# IMU_Sensor.net
KiCad netlist of a schematic drawn in Altium Designer
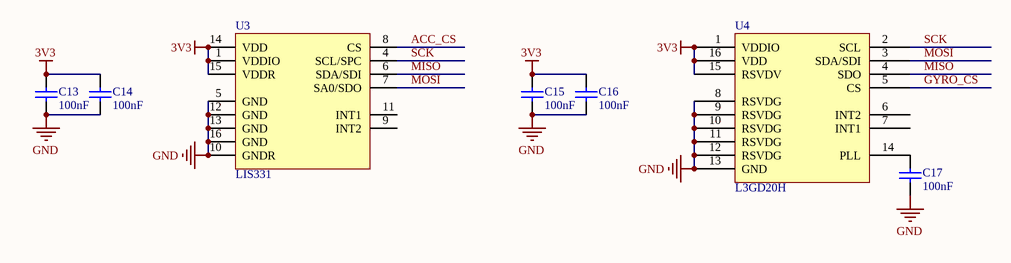
[diagram p0: IMU Sensor.SchDoc]

(export (version "E")
  (design (tool "Eeschema 10.0.6"))
  (components
    (comp (ref "C13")
      (value "100nF")
      (footprint "0603-CAP")
      (description "Capacitor")
      (fields (field (name "PUBLISHER") "Altium Limited"))
      (libsource (lib "BarelangRobotics") (part "Cap"))
    )
    (comp (ref "C14")
      (value "100nF")
      (footprint "0603-CAP")
      (description "Capacitor")
      (fields (field (name "PUBLISHER") "Altium Limited"))
      (libsource (lib "BarelangRobotics") (part "Cap"))
    )
    (comp (ref "C15")
      (value "100nF")
      (footprint "0603-CAP")
      (description "Capacitor")
      (fields (field (name "PUBLISHER") "Altium Limited"))
      (libsource (lib "BarelangRobotics") (part "Cap"))
    )
    (comp (ref "C16")
      (value "100nF")
      (footprint "0603-CAP")
      (description "Capacitor")
      (fields (field (name "PUBLISHER") "Altium Limited"))
      (libsource (lib "BarelangRobotics") (part "Cap"))
    )
    (comp (ref "C17")
      (value "100nF")
      (footprint "0603-CAP")
      (description "Capacitor")
      (fields (field (name "PUBLISHER") "Altium Limited"))
      (libsource (lib "BarelangRobotics") (part "Cap"))
    )
    (comp (ref "U3")
      (value "LIS331")
      (footprint "LGA16-3MM")
      (libsource (lib "BarelangRobotics") (part "LIS331"))
    )
    (comp (ref "U4")
      (value "L3GD20H")
      (footprint "LGA16-3MM")
      (libsource (lib "BarelangRobotics") (part "L3GD20H"))
    )
  )
  (nets
    (net (code "1") (name "/ACC_CS") (class "Default")
      (node (ref "U3") (pin "8") (pinfunction "CS_8") (pintype "passive"))
    )
    (net (code "2") (name "/GYRO_CS") (class "Default")
      (node (ref "U4") (pin "5") (pinfunction "CS_5") (pintype "passive"))
    )
    (net (code "3") (name "/MISO") (class "Default")
      (node (ref "U3") (pin "6") (pinfunction "SDA/SDI_6") (pintype "passive"))
      (node (ref "U4") (pin "4") (pinfunction "SDO_4") (pintype "passive"))
    )
    (net (code "4") (name "/MOSI") (class "Default")
      (node (ref "U3") (pin "7") (pinfunction "SA0/SDO_7") (pintype "passive"))
      (node (ref "U4") (pin "3") (pinfunction "SDA/SDI_3") (pintype "passive"))
    )
    (net (code "5") (name "/SCK") (class "Default")
      (node (ref "U3") (pin "4") (pinfunction "SCL/SPC_4") (pintype "passive"))
      (node (ref "U4") (pin "2") (pinfunction "SCL_2") (pintype "passive"))
    )
    (net (code "6") (name "3V3") (class "Default")
      (node (ref "C13") (pin "2") (pinfunction "2_2") (pintype "passive"))
      (node (ref "C14") (pin "2") (pinfunction "2_2") (pintype "passive"))
      (node (ref "C15") (pin "2") (pinfunction "2_2") (pintype "passive"))
      (node (ref "C16") (pin "2") (pinfunction "2_2") (pintype "passive"))
      (node (ref "U3") (pin "1") (pinfunction "VDDIO_1") (pintype "passive"))
      (node (ref "U3") (pin "14") (pinfunction "VDD_14") (pintype "passive"))
      (node (ref "U3") (pin "15") (pinfunction "VDDR_15") (pintype "passive"))
      (node (ref "U4") (pin "1") (pinfunction "VDDIO_1") (pintype "passive"))
      (node (ref "U4") (pin "15") (pinfunction "RSVDV_15") (pintype "passive"))
      (node (ref "U4") (pin "16") (pinfunction "VDD_16") (pintype "passive"))
    )
    (net (code "7") (name "GND") (class "Default")
      (node (ref "C13") (pin "1") (pinfunction "1_1") (pintype "passive"))
      (node (ref "C14") (pin "1") (pinfunction "1_1") (pintype "passive"))
      (node (ref "C15") (pin "1") (pinfunction "1_1") (pintype "passive"))
      (node (ref "C16") (pin "1") (pinfunction "1_1") (pintype "passive"))
      (node (ref "C17") (pin "1") (pinfunction "1_1") (pintype "passive"))
      (node (ref "U3") (pin "10") (pinfunction "GNDR_10") (pintype "passive"))
      (node (ref "U3") (pin "12") (pinfunction "GND_12") (pintype "passive"))
      (node (ref "U3") (pin "13") (pinfunction "GND_13") (pintype "passive"))
      (node (ref "U3") (pin "16") (pinfunction "GND_16") (pintype "passive"))
      (node (ref "U3") (pin "5") (pinfunction "GND_5") (pintype "passive"))
      (node (ref "U4") (pin "10") (pinfunction "RSVDG_10") (pintype "passive"))
      (node (ref "U4") (pin "11") (pinfunction "RSVDG_11") (pintype "passive"))
      (node (ref "U4") (pin "12") (pinfunction "RSVDG_12") (pintype "passive"))
      (node (ref "U4") (pin "13") (pinfunction "GND_13") (pintype "passive"))
      (node (ref "U4") (pin "8") (pinfunction "RSVDG_8") (pintype "passive"))
      (node (ref "U4") (pin "9") (pinfunction "RSVDG_9") (pintype "passive"))
    )
    (net (code "8") (name "Net-(U4-PLL)") (class "Default")
      (node (ref "C17") (pin "2") (pinfunction "2_2") (pintype "passive"))
      (node (ref "U4") (pin "14") (pinfunction "PLL_14") (pintype "passive"))
    )
    (net (code "9") (name "unconnected-(U3-INT1-Pad11)") (class "Default")
      (node (ref "U3") (pin "11") (pinfunction "INT1_11") (pintype "passive"))
    )
    (net (code "10") (name "unconnected-(U3-INT2-Pad9)") (class "Default")
      (node (ref "U3") (pin "9") (pinfunction "INT2_9") (pintype "passive"))
    )
    (net (code "11") (name "unconnected-(U4-INT1-Pad7)") (class "Default")
      (node (ref "U4") (pin "7") (pinfunction "INT1_7") (pintype "passive"))
    )
    (net (code "12") (name "unconnected-(U4-INT2-Pad6)") (class "Default")
      (node (ref "U4") (pin "6") (pinfunction "INT2_6") (pintype "passive"))
    )
  )
)
